# MCU.net
KiCad netlist of a schematic drawn in Altium Designer
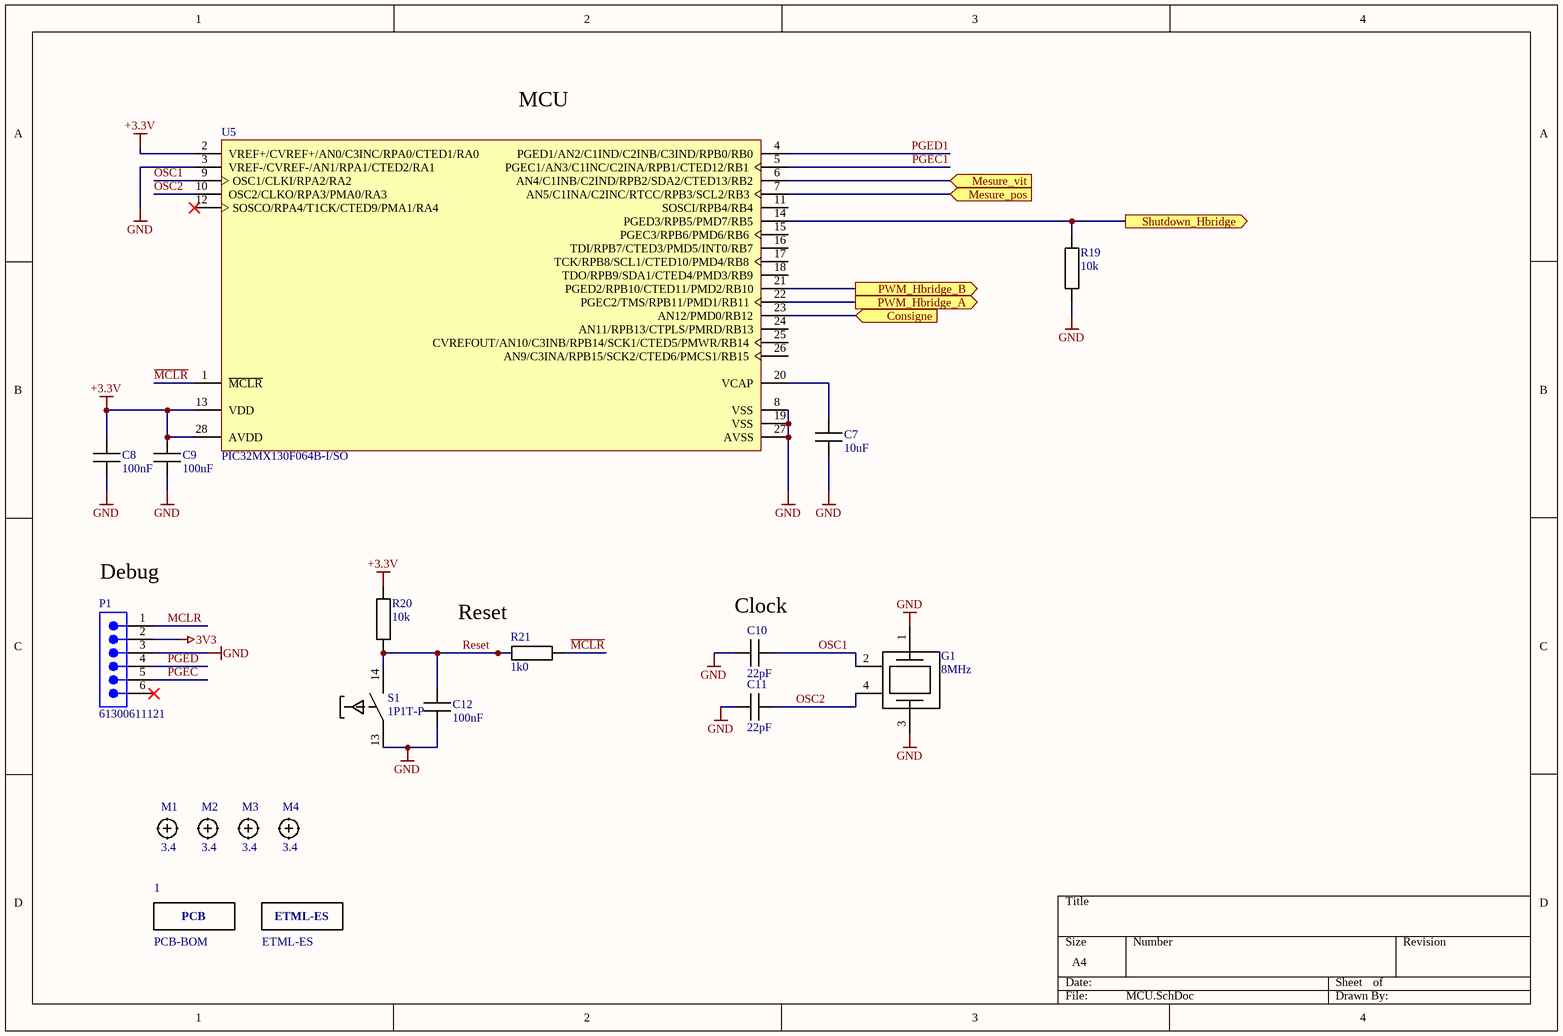
[diagram p0: MCU.SchDoc]

(export (version "E")
  (design (tool "Eeschema 10.0.6"))
  (components
    (comp (ref "1")
      (value "PCB-BOM")
      (description "PCB element for BOM")
      (libsource (lib "ETML-ES") (part "DRAW-PCB-BOM"))
    )
    (comp (ref "2")
      (value "ETML-ES")
      (footprint "ETML-ES-CU-Footprint-1")
      (description "Logo ETML-ES")
      (libsource (lib "ETML-ES") (part "DRAW-ETML-CU"))
    )
    (comp (ref "C7")
      (value "10uF")
      (footprint "CAPC2012X08M")
      (description "CAPC 10uF X5R 16V 10% 2012 (0805 INCH)")
      (fields (field (name "TOLERANCE") "±10%") (field (name "VOLTAGE") "16V"))
      (libsource (lib "ETML-ES") (part "CAP"))
    )
    (comp (ref "C8")
      (value "100nF")
      (footprint "CAPC2012X08M")
      (description "CAPC 100nF X7R 50V 10% 2012 (0805 INCH)")
      (fields (field (name "VOLTAGE") "50V") (field (name "MANUFACTURER") "TDK"))
      (libsource (lib "ETML-ES") (part "CAP"))
    )
    (comp (ref "C9")
      (value "100nF")
      (footprint "CAPC2012X08M")
      (description "CAPC 100nF X7R 50V 10% 2012 (0805 INCH)")
      (fields (field (name "VOLTAGE") "50V") (field (name "MANUFACTURER") "TDK"))
      (libsource (lib "ETML-ES") (part "CAP"))
    )
    (comp (ref "C10")
      (value "22pF")
      (footprint "CAPC2012X08M")
      (description "CAPC 100nF X7R 50V 10% 2012 (0805 INCH)")
      (fields (field (name "VOLTAGE") "50V") (field (name "MANUFACTURER") "TDK"))
      (libsource (lib "ETML-ES") (part "CAP"))
    )
    (comp (ref "C11")
      (value "22pF")
      (footprint "CAPC2012X08M")
      (description "CAPC 100nF X7R 50V 10% 2012 (0805 INCH)")
      (fields (field (name "VOLTAGE") "50V") (field (name "MANUFACTURER") "TDK"))
      (libsource (lib "ETML-ES") (part "CAP"))
    )
    (comp (ref "C12")
      (value "100nF")
      (footprint "CAPC2012X08M")
      (description "CAPC 100nF X7R 50V 10% 2012 (0805 INCH)")
      (fields (field (name "VOLTAGE") "50V") (field (name "MANUFACTURER") "TDK"))
      (libsource (lib "ETML-ES") (part "CAP"))
    )
    (comp (ref "G1")
      (value "8MHz")
      (footprint "OSC60X35X10")
      (description "CRYSTAL 8MHz 6.0x3.5mm")
      (fields (field (name "TOLERANCE") "±30ppm") (field (name "MANUFACTURER") "Farnell Multicomp"))
      (libsource (lib "ETML-ES") (part "OSC-CRYSTAL-SHIELDED"))
    )
    (comp (ref "M1")
      (value "3.4")
      (footprint "MECH-UHD340")
      (description "Unplated Hole 3.4mm")
      (libsource (lib "ETML-ES") (part "MECH-UH"))
    )
    (comp (ref "M2")
      (value "3.4")
      (footprint "MECH-UHD340")
      (description "Unplated Hole 3.4mm")
      (libsource (lib "ETML-ES") (part "MECH-UH"))
    )
    (comp (ref "M3")
      (value "3.4")
      (footprint "MECH-UHD340")
      (description "Unplated Hole 3.4mm")
      (libsource (lib "ETML-ES") (part "MECH-UH"))
    )
    (comp (ref "M4")
      (value "3.4")
      (footprint "MECH-UHD340")
      (description "Unplated Hole 3.4mm")
      (libsource (lib "ETML-ES") (part "MECH-UH"))
    )
    (comp (ref "P1")
      (value "61300611121")
      (footprint "61300611121")
      (libsource (lib "Altium Content Vault") (part "Header_Male_1R_06P"))
    )
    (comp (ref "R19")
      (value "10k")
      (footprint "RESC2012X06M")
      (description "RES 10kohm  ±1% 0.125W 2012 (0805 INCH)")
      (fields (field (name "TOLERANCE") "±1%") (field (name "VOLTAGE") "150V"))
      (libsource (lib "ETML-ES") (part "RES"))
    )
    (comp (ref "R20")
      (value "10k")
      (footprint "RESC2012X06M")
      (description "RES 10kohm  ±1% 0.125W 2012 (0805 INCH)")
      (fields (field (name "TOLERANCE") "±1%") (field (name "VOLTAGE") "150V"))
      (libsource (lib "ETML-ES") (part "RES"))
    )
    (comp (ref "R21")
      (value "1k0")
      (footprint "RESC2012X06M")
      (description "RES 1.0kohm  ±1% 0.125W 2012 (0805 INCH)")
      (fields (field (name "MANUFACTURER") "Yageo") (field (name "TOLERANCE") "±1%"))
      (libsource (lib "ETML-ES") (part "RES"))
    )
    (comp (ref "S1")
      (value "1P1T-P")
      (footprint "TE_1825910-6")
      (description "SW 600X600X500 24V 50mA THT")
      (fields (field (name "VOLTAGE") "24V") (field (name "MANUFACTURER") "TE Connectivity"))
      (libsource (lib "ETML-ES") (part "SWI-1P1T-P"))
    )
    (comp (ref "U5")
      (value "PIC32MX130F064B-I/SO")
      (footprint "MCHP-SOIC-SO28_L")
      (fields (field (name "MANUFACTURER") "Microchip"))
      (libsource (lib "Altium Content Vault") (part "MCHP-PIC32MX1X0FXXXB-28"))
    )
  )
  (nets
    (net (code "1") (name "+3.3V") (class "Default")
      (node (ref "C8") (pin "2") (pinfunction "2_2") (pintype "passive"))
      (node (ref "C9") (pin "2") (pinfunction "2_2") (pintype "passive"))
      (node (ref "R20") (pin "2") (pinfunction "2_2") (pintype "passive"))
      (node (ref "U5") (pin "13") (pinfunction "VDD_13") (pintype "passive"))
      (node (ref "U5") (pin "2") (pinfunction "VREF+/CVREF+/AN0/C3INC/RPA0/CTED1/RA0_2") (pintype "passive"))
      (node (ref "U5") (pin "28") (pinfunction "AVDD_28") (pintype "passive"))
    )
    (net (code "2") (name "/Consigne") (class "Default")
      (node (ref "U5") (pin "23") (pinfunction "AN12/PMD0/RB12_23") (pintype "passive"))
    )
    (net (code "3") (name "/MCLR") (class "Default")
      (node (ref "P1") (pin "1") (pinfunction "1_1") (pintype "passive"))
    )
    (net (code "4") (name "/Mesure_pos") (class "Default")
      (node (ref "U5") (pin "7") (pinfunction "AN5/C1INA/C2INC/RTCC/RPB3/SCL2/RB3_7") (pintype "passive"))
    )
    (net (code "5") (name "/Mesure_vit") (class "Default")
      (node (ref "U5") (pin "6") (pinfunction "AN4/C1INB/C2IND/RPB2/SDA2/CTED13/RB2_6") (pintype "passive"))
    )
    (net (code "6") (name "/OSC1") (class "Default")
      (node (ref "C10") (pin "1") (pinfunction "1_1") (pintype "passive"))
      (node (ref "G1") (pin "2") (pinfunction "2_2") (pintype "passive"))
      (node (ref "U5") (pin "9") (pinfunction "OSC1/CLKI/RPA2/RA2_9") (pintype "passive"))
    )
    (net (code "7") (name "/OSC2") (class "Default")
      (node (ref "C11") (pin "1") (pinfunction "1_1") (pintype "passive"))
      (node (ref "G1") (pin "4") (pinfunction "4_4") (pintype "passive"))
      (node (ref "U5") (pin "10") (pinfunction "OSC2/CLKO/RPA3/PMA0/RA3_10") (pintype "passive"))
    )
    (net (code "8") (name "/PGEC") (class "Default")
      (node (ref "P1") (pin "5") (pinfunction "5_5") (pintype "passive"))
    )
    (net (code "9") (name "/PGEC1") (class "Default")
      (node (ref "U5") (pin "5") (pinfunction "PGEC1/AN3/C1INC/C2INA/RPB1/CTED12/RB1_5") (pintype "passive"))
    )
    (net (code "10") (name "/PGED") (class "Default")
      (node (ref "P1") (pin "4") (pinfunction "4_4") (pintype "passive"))
    )
    (net (code "11") (name "/PGED1") (class "Default")
      (node (ref "U5") (pin "4") (pinfunction "PGED1/AN2/C1IND/C2INB/C3IND/RPB0/RB0_4") (pintype "passive"))
    )
    (net (code "12") (name "/PWM_Hbridge_A") (class "Default")
      (node (ref "U5") (pin "22") (pinfunction "PGEC2/TMS/RPB11/PMD1/RB11_22") (pintype "passive"))
    )
    (net (code "13") (name "/PWM_Hbridge_B") (class "Default")
      (node (ref "U5") (pin "21") (pinfunction "PGED2/RPB10/CTED11/PMD2/RB10_21") (pintype "passive"))
    )
    (net (code "14") (name "/Reset") (class "Default")
      (node (ref "C12") (pin "2") (pinfunction "2_2") (pintype "passive"))
      (node (ref "R20") (pin "1") (pinfunction "1_1") (pintype "passive"))
      (node (ref "R21") (pin "1") (pinfunction "1_1") (pintype "passive"))
      (node (ref "S1") (pin "14") (pinfunction "14_14") (pintype "passive"))
    )
    (net (code "15") (name "/Shutdown_Hbridge") (class "Default")
      (node (ref "R19") (pin "2") (pinfunction "2_2") (pintype "passive"))
      (node (ref "U5") (pin "14") (pinfunction "PGED3/RPB5/PMD7/RB5_14") (pintype "passive"))
    )
    (net (code "16") (name "/~{MCLR}") (class "Default")
      (node (ref "R21") (pin "2") (pinfunction "2_2") (pintype "passive"))
      (node (ref "U5") (pin "1") (pinfunction "~{MCLR}_1") (pintype "passive"))
    )
    (net (code "17") (name "3V3") (class "Default")
      (node (ref "P1") (pin "2") (pinfunction "2_2") (pintype "passive"))
    )
    (net (code "18") (name "GND") (class "Default")
      (node (ref "C10") (pin "2") (pinfunction "2_2") (pintype "passive"))
      (node (ref "C11") (pin "2") (pinfunction "2_2") (pintype "passive"))
      (node (ref "C12") (pin "1") (pinfunction "1_1") (pintype "passive"))
      (node (ref "C7") (pin "1") (pinfunction "1_1") (pintype "passive"))
      (node (ref "C8") (pin "1") (pinfunction "1_1") (pintype "passive"))
      (node (ref "C9") (pin "1") (pinfunction "1_1") (pintype "passive"))
      (node (ref "G1") (pin "1") (pinfunction "1_1") (pintype "passive"))
      (node (ref "G1") (pin "3") (pinfunction "3_3") (pintype "passive"))
      (node (ref "P1") (pin "3") (pinfunction "3_3") (pintype "passive"))
      (node (ref "R19") (pin "1") (pinfunction "1_1") (pintype "passive"))
      (node (ref "S1") (pin "13") (pinfunction "13_13") (pintype "passive"))
      (node (ref "U5") (pin "19") (pinfunction "VSS_19") (pintype "passive"))
      (node (ref "U5") (pin "27") (pinfunction "AVSS_27") (pintype "passive"))
      (node (ref "U5") (pin "3") (pinfunction "VREF-/CVREF-/AN1/RPA1/CTED2/RA1_3") (pintype "passive"))
      (node (ref "U5") (pin "8") (pinfunction "VSS_8") (pintype "passive"))
    )
    (net (code "19") (name "Net-(U5-VCAP)") (class "Default")
      (node (ref "C7") (pin "2") (pinfunction "2_2") (pintype "passive"))
      (node (ref "U5") (pin "20") (pinfunction "VCAP_20") (pintype "passive"))
    )
    (net (code "20") (name "unconnected-(P1-Pad6)") (class "Default")
      (node (ref "P1") (pin "6") (pinfunction "6_6") (pintype "passive+no_connect"))
    )
    (net (code "21") (name "unconnected-(U5-AN9{slash}C3INA{slash}RPB15{slash}SCK2{slash}CTED6{slash}PMCS1{slash}RB15-Pad26)") (class "Default")
      (node (ref "U5") (pin "26") (pinfunction "AN9/C3INA/RPB15/SCK2/CTED6/PMCS1/RB15_26") (pintype "passive"))
    )
    (net (code "22") (name "unconnected-(U5-AN11{slash}RPB13{slash}CTPLS{slash}PMRD{slash}RB13-Pad24)") (class "Default")
      (node (ref "U5") (pin "24") (pinfunction "AN11/RPB13/CTPLS/PMRD/RB13_24") (pintype "passive"))
    )
    (net (code "23") (name "unconnected-(U5-CVREFOUT{slash}AN10{slash}C3INB{slash}RPB14{slash}SCK1{slash}CTED5{slash}PMWR{slash}RB14-Pad25)") (class "Default")
      (node (ref "U5") (pin "25") (pinfunction "CVREFOUT/AN10/C3INB/RPB14/SCK1/CTED5/PMWR/RB14_25") (pintype "passive"))
    )
    (net (code "24") (name "unconnected-(U5-PGEC3{slash}RPB6{slash}PMD6{slash}RB6-Pad15)") (class "Default")
      (node (ref "U5") (pin "15") (pinfunction "PGEC3/RPB6/PMD6/RB6_15") (pintype "passive"))
    )
    (net (code "25") (name "unconnected-(U5-SOSCI{slash}RPB4{slash}RB4-Pad11)") (class "Default")
      (node (ref "U5") (pin "11") (pinfunction "SOSCI/RPB4/RB4_11") (pintype "passive"))
    )
    (net (code "26") (name "unconnected-(U5-SOSCO{slash}RPA4{slash}T1CK{slash}CTED9{slash}PMA1{slash}RA4-Pad12)") (class "Default")
      (node (ref "U5") (pin "12") (pinfunction "SOSCO/RPA4/T1CK/CTED9/PMA1/RA4_12") (pintype "passive+no_connect"))
    )
    (net (code "27") (name "unconnected-(U5-TCK{slash}RPB8{slash}SCL1{slash}CTED10{slash}PMD4{slash}RB8-Pad17)") (class "Default")
      (node (ref "U5") (pin "17") (pinfunction "TCK/RPB8/SCL1/CTED10/PMD4/RB8_17") (pintype "passive"))
    )
    (net (code "28") (name "unconnected-(U5-TDI{slash}RPB7{slash}CTED3{slash}PMD5{slash}INT0{slash}RB7-Pad16)") (class "Default")
      (node (ref "U5") (pin "16") (pinfunction "TDI/RPB7/CTED3/PMD5/INT0/RB7_16") (pintype "passive"))
    )
    (net (code "29") (name "unconnected-(U5-TDO{slash}RPB9{slash}SDA1{slash}CTED4{slash}PMD3{slash}RB9-Pad18)") (class "Default")
      (node (ref "U5") (pin "18") (pinfunction "TDO/RPB9/SDA1/CTED4/PMD3/RB9_18") (pintype "passive"))
    )
  )
)
